# SCHE_B555.net
KiCad netlist of a schematic drawn in Altium Designer
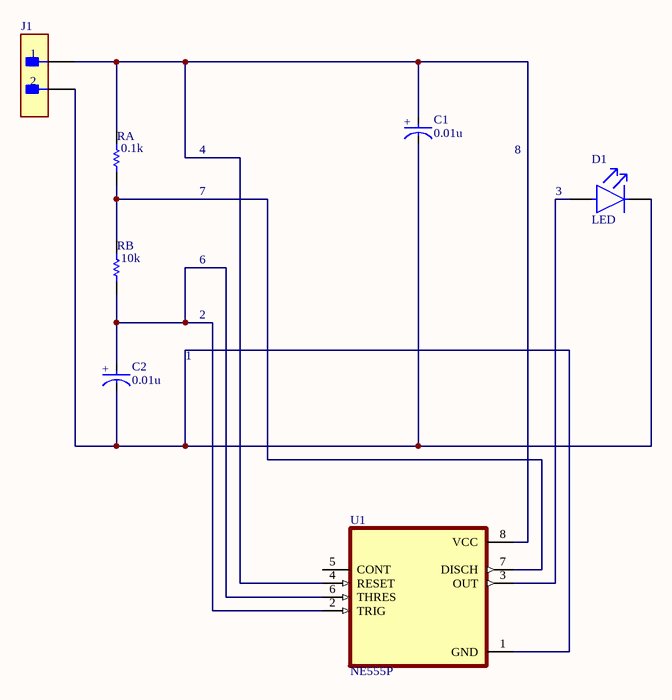
[diagram p0: SCHE_B555.SchDoc]

(export (version "E")
  (design (tool "Eeschema 10.0.6"))
  (components
    (comp (ref "C1")
      (value "0.01u")
      (footprint "FP-RAD-TH-D_16_0_5-L_31_5-MFG")
      (fields (field (name "TOLERANCE") "20%") (field (name "VOLTAGE") "50V"))
      (libsource (lib "Altium Content Vault") (part "203bc49f2ac43e59fd269a8c329ed05"))
    )
    (comp (ref "C2")
      (value "0.01u")
      (footprint "FP-RAD-TH-D_16_0_5-L_31_5-MFG")
      (fields (field (name "TOLERANCE") "20%") (field (name "VOLTAGE") "50V"))
      (libsource (lib "Altium Content Vault") (part "203bc49f2ac43e59fd269a8c329ed05"))
    )
    (comp (ref "D1")
      (value "LED")
      (footprint "FP-HLMP-1301-MFG")
      (fields
        (field (name "MANUFACTURER PART NUMBER") "HLMP-1301")
        (field (name "OCTOPART") "https://octopart.com/hlmp-1301-broadcom-71130345")
        (field (name "MANUFACTURER") "Broadcom")
      )
      (libsource (lib "Altium Content Vault") (part "8706943c75ba83719d021d2fdc84c58"))
    )
    (comp (ref "J1")
      (value "~")
      (footprint "FP-M20-9990246-MFG")
      (description "{1 to V_CC , 2 to GND}")
      (fields
        (field (name "OCTOPART") "https://octopart.com/m20-9990246-harwin-2590635")
        (field (name "MANUFACTURER") "Harwin")
      )
      (libsource (lib "Altium Content Vault") (part "3bc925449376181038e59eaffc5286c"))
    )
    (comp (ref "RA")
      (value "0.1k")
      (footprint "RESA60-630X240")
      (fields (field (name "TOLERANCE") "20%"))
      (libsource (lib "Altium Content Vault") (part "RES-2"))
    )
    (comp (ref "RB")
      (value "10k")
      (footprint "RESA60-630X240")
      (fields (field (name "TOLERANCE") "20%"))
      (libsource (lib "Altium Content Vault") (part "RES-2"))
    )
    (comp (ref "U1")
      (value "NE555P")
      (footprint "DIP794W45P254L959H508Q8")
      (libsource (lib "NE555P") (part "NE555P"))
    )
  )
  (nets
    (net (code "1") (name "Net-(C1-A)") (class "Default")
      (node (ref "C1") (pin "2") (pinfunction "A_2") (pintype "passive"))
      (node (ref "J1") (pin "1") (pinfunction "1_1") (pintype "passive"))
      (node (ref "RA") (pin "1") (pinfunction "1_1") (pintype "passive"))
      (node (ref "U1") (pin "4") (pinfunction "RESET_4") (pintype "input"))
      (node (ref "U1") (pin "8") (pinfunction "VCC_8") (pintype "power_in"))
    )
    (net (code "2") (name "Net-(C1-C)") (class "Default")
      (node (ref "C1") (pin "1") (pinfunction "C_1") (pintype "passive"))
      (node (ref "C2") (pin "1") (pinfunction "C_1") (pintype "passive"))
      (node (ref "D1") (pin "1") (pinfunction "C_1") (pintype "passive"))
      (node (ref "J1") (pin "2") (pinfunction "2_2") (pintype "passive"))
      (node (ref "U1") (pin "1") (pinfunction "GND_1") (pintype "power_in"))
    )
    (net (code "3") (name "Net-(C2-A)") (class "Default")
      (node (ref "C2") (pin "2") (pinfunction "A_2") (pintype "passive"))
      (node (ref "RB") (pin "2") (pinfunction "2_2") (pintype "passive"))
      (node (ref "U1") (pin "2") (pinfunction "TRIG_2") (pintype "input"))
      (node (ref "U1") (pin "6") (pinfunction "THRES_6") (pintype "input"))
    )
    (net (code "4") (name "Net-(D1-A)") (class "Default")
      (node (ref "D1") (pin "2") (pinfunction "A_2") (pintype "passive"))
      (node (ref "U1") (pin "3") (pinfunction "OUT_3") (pintype "output"))
    )
    (net (code "5") (name "Net-(U1-DISCH)") (class "Default")
      (node (ref "RA") (pin "2") (pinfunction "2_2") (pintype "passive"))
      (node (ref "RB") (pin "1") (pinfunction "1_1") (pintype "passive"))
      (node (ref "U1") (pin "7") (pinfunction "DISCH_7") (pintype "output"))
    )
    (net (code "6") (name "unconnected-(U1-CONT-Pad5)") (class "Default")
      (node (ref "U1") (pin "5") (pinfunction "CONT_5") (pintype "passive"))
    )
  )
)
